# Orange_pi_zero.net
KiCad netlist of a schematic drawn in Altium Designer
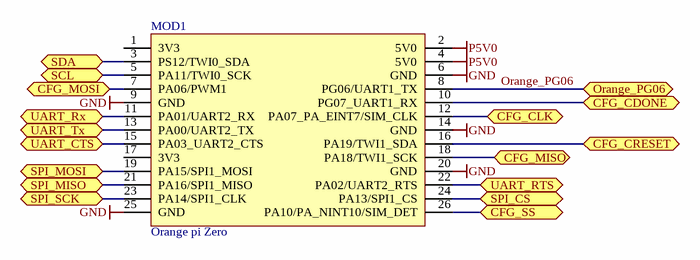
[diagram p0: Orange_pi_zero.SchDoc]

(export (version "E")
  (design (tool "Eeschema 10.0.6"))
  (components
    (comp (ref "MOD1")
      (value "Orange pi Zero")
      (footprint "MOD_Orange_pi_Zero")
      (libsource (lib "LIBRARY_SCH") (part "MOD_Orange_pi_Zero"))
    )
  )
  (nets
    (net (code "1") (name "/CFG_CDONE") (class "Default")
      (node (ref "MOD1") (pin "10") (pinfunction "PG07_UART1_RX_10") (pintype "passive"))
    )
    (net (code "2") (name "/CFG_CLK") (class "Default")
      (node (ref "MOD1") (pin "12") (pinfunction "PA07_PA_EINT7/SIM_CLK_12") (pintype "passive"))
    )
    (net (code "3") (name "/CFG_CRESET") (class "Default")
      (node (ref "MOD1") (pin "16") (pinfunction "PA19/TWI1_SDA_16") (pintype "passive"))
    )
    (net (code "4") (name "/CFG_MISO") (class "Default")
      (node (ref "MOD1") (pin "18") (pinfunction "PA18/TWI1_SCK_18") (pintype "passive"))
    )
    (net (code "5") (name "/CFG_MOSI") (class "Default")
      (node (ref "MOD1") (pin "7") (pinfunction "PA06/PWM1_7") (pintype "passive"))
    )
    (net (code "6") (name "/CFG_SS") (class "Default")
      (node (ref "MOD1") (pin "26") (pinfunction "PA10/PA_NINT10/SIM_DET_26") (pintype "passive"))
    )
    (net (code "7") (name "/Orange_PG06") (class "Default")
      (node (ref "MOD1") (pin "8") (pinfunction "PG06/UART1_TX_8") (pintype "passive"))
    )
    (net (code "8") (name "/SCL") (class "Default")
      (node (ref "MOD1") (pin "5") (pinfunction "PA11/TWI0_SCK_5") (pintype "passive"))
    )
    (net (code "9") (name "/SDA") (class "Default")
      (node (ref "MOD1") (pin "3") (pinfunction "PS12/TWI0_SDA_3") (pintype "passive"))
    )
    (net (code "10") (name "/SPI_CS") (class "Default")
      (node (ref "MOD1") (pin "24") (pinfunction "PA13/SPI1_CS_24") (pintype "passive"))
    )
    (net (code "11") (name "/SPI_MISO") (class "Default")
      (node (ref "MOD1") (pin "21") (pinfunction "PA16/SPI1_MISO_21") (pintype "passive"))
    )
    (net (code "12") (name "/SPI_MOSI") (class "Default")
      (node (ref "MOD1") (pin "19") (pinfunction "PA15/SPI1_MOSI_19") (pintype "passive"))
    )
    (net (code "13") (name "/SPI_SCK") (class "Default")
      (node (ref "MOD1") (pin "23") (pinfunction "PA14/SPI1_CLK_23") (pintype "passive"))
    )
    (net (code "14") (name "/UART_CTS") (class "Default")
      (node (ref "MOD1") (pin "15") (pinfunction "PA03_UART2_CTS_15") (pintype "passive"))
    )
    (net (code "15") (name "/UART_RTS") (class "Default")
      (node (ref "MOD1") (pin "22") (pinfunction "PA02/UART2_RTS_22") (pintype "passive"))
    )
    (net (code "16") (name "/UART_Rx") (class "Default")
      (node (ref "MOD1") (pin "11") (pinfunction "PA01/UART2_RX_11") (pintype "passive"))
    )
    (net (code "17") (name "/UART_Tx") (class "Default")
      (node (ref "MOD1") (pin "13") (pinfunction "PA00/UART2_TX_13") (pintype "passive"))
    )
    (net (code "18") (name "GND") (class "Default")
      (node (ref "MOD1") (pin "14") (pinfunction "GND_14") (pintype "passive"))
      (node (ref "MOD1") (pin "20") (pinfunction "GND_20") (pintype "passive"))
      (node (ref "MOD1") (pin "25") (pinfunction "GND_25") (pintype "passive"))
      (node (ref "MOD1") (pin "6") (pinfunction "GND_6") (pintype "passive"))
      (node (ref "MOD1") (pin "9") (pinfunction "GND_9") (pintype "passive"))
    )
    (net (code "19") (name "P5V0") (class "Default")
      (node (ref "MOD1") (pin "2") (pinfunction "5V0_2") (pintype "passive"))
      (node (ref "MOD1") (pin "4") (pinfunction "5V0_4") (pintype "passive"))
    )
    (net (code "20") (name "unconnected-(MOD1-3V3-Pad1)") (class "Default")
      (node (ref "MOD1") (pin "1") (pinfunction "3V3_1") (pintype "passive"))
    )
    (net (code "21") (name "unconnected-(MOD1-3V3-Pad17)") (class "Default")
      (node (ref "MOD1") (pin "17") (pinfunction "3V3_17") (pintype "passive"))
    )
  )
)
